# USB.net
KiCad netlist of a schematic drawn in Altium Designer
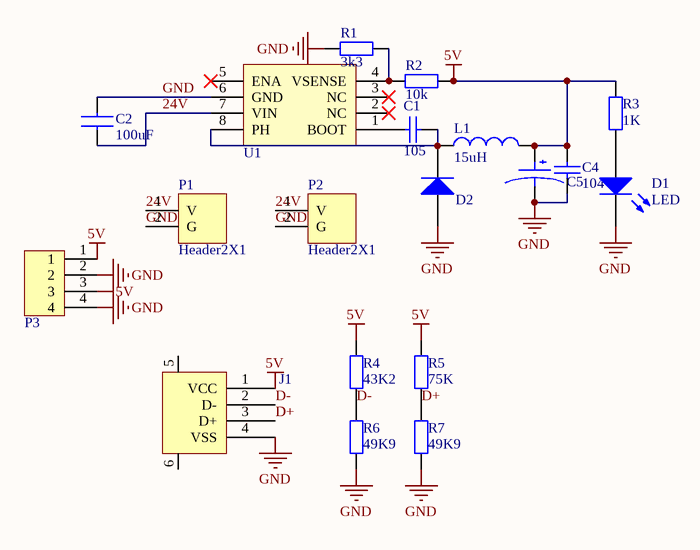
[diagram p0: USB转接板.SchDoc]

(export (version "E")
  (design (tool "Eeschema 10.0.6"))
  (components
    (comp (ref "C1")
      (value "105")
      (footprint "0603C")
      (description "0603/0805")
      (libsource (lib "SHAWN") (part "C_106"))
    )
    (comp (ref "C2") (value "100uF") (footprint "1201C") (libsource (lib "SHAWN") (part "CAP100uF")))
    (comp (ref "C4")
      (value "104")
      (footprint "0603C")
      (description "0603/0805")
      (libsource (lib "SHAWN") (part "C_104"))
    )
    (comp (ref "C5")
      (value "CAP_钽220")
      (footprint "cap_钽E封装")
      (description "CAP")
      (libsource (lib "SHAWN") (part "CAP_钽220"))
    )
    (comp (ref "D1") (value "LED") (footprint "LED_0603") (libsource (lib "SHAWN") (part "LED")))
    (comp (ref "D2")
      (value "Diode_SS34")
      (footprint "Diode_SS34")
      (description "肖特基二极管")
      (libsource (lib "SHAWN") (part "Diode_SS34"))
    )
    (comp (ref "J1")
      (value "USB_seat")
      (footprint "USB_SEAT")
      (description "母座")
      (libsource (lib "SHAWN") (part "USB_seat"))
    )
    (comp (ref "L1")
      (value "15uH")
      (footprint "Inductor7.2X7.2")
      (description "屏蔽电感")
      (libsource (lib "SHAWN") (part "Inductor"))
    )
    (comp (ref "P1")
      (value "Header2X1")
      (footprint "Header_PWR_seat")
      (description "power")
      (libsource (lib "SHAWN") (part "Header2X1"))
    )
    (comp (ref "P2")
      (value "Header2X1")
      (footprint "Header_PWR_seat")
      (description "power")
      (libsource (lib "SHAWN") (part "Header2X1"))
    )
    (comp (ref "P3") (value "Header4") (footprint "Header4_white") (libsource (lib "SHAWN") (part "Header4")))
    (comp (ref "R1")
      (value "3k3")
      (footprint "0603R")
      (description "0603/0805")
      (libsource (lib "") (part "R_1"))
    )
    (comp (ref "R2")
      (value "10k")
      (footprint "0603R")
      (description "0603/0805")
      (libsource (lib "") (part "R_1"))
    )
    (comp (ref "R3")
      (value "1K")
      (footprint "0603R")
      (description "0603/0805")
      (libsource (lib "SHAWN") (part "R"))
    )
    (comp (ref "R4")
      (value "43K2")
      (footprint "0603R")
      (description "0603/0805")
      (libsource (lib "SHAWN") (part "R"))
    )
    (comp (ref "R5")
      (value "75K")
      (footprint "0603R")
      (description "0603/0805")
      (libsource (lib "SHAWN") (part "R"))
    )
    (comp (ref "R6")
      (value "49K9")
      (footprint "0603R")
      (description "0603/0805")
      (libsource (lib "SHAWN") (part "R"))
    )
    (comp (ref "R7")
      (value "49K9")
      (footprint "0603R")
      (description "0603/0805")
      (libsource (lib "SHAWN") (part "R"))
    )
    (comp (ref "U1")
      (value "TPS5430/5450")
      (footprint "TPS5430")
      (description "降压")
      (libsource (lib "SHAWN") (part "TPS5430/5450"))
    )
  )
  (nets
    (net (code "1") (name "/24V") (class "Default")
      (node (ref "C2") (pin "1") (pinfunction "1_1") (pintype "passive"))
      (node (ref "P1") (pin "1") (pinfunction "V_1") (pintype "passive"))
      (node (ref "P2") (pin "1") (pinfunction "V_1") (pintype "passive"))
      (node (ref "U1") (pin "7") (pinfunction "VIN_7") (pintype "passive"))
    )
    (net (code "2") (name "/D+") (class "Default")
      (node (ref "J1") (pin "3") (pinfunction "D+_3") (pintype "passive"))
      (node (ref "R5") (pin "1") (pinfunction "1_1") (pintype "passive"))
      (node (ref "R7") (pin "2") (pinfunction "2_2") (pintype "passive"))
    )
    (net (code "3") (name "/D-") (class "Default")
      (node (ref "J1") (pin "2") (pinfunction "D-_2") (pintype "passive"))
      (node (ref "R4") (pin "1") (pinfunction "1_1") (pintype "passive"))
      (node (ref "R6") (pin "2") (pinfunction "2_2") (pintype "passive"))
    )
    (net (code "4") (name "5V") (class "Default")
      (node (ref "C4") (pin "2") (pinfunction "2_2") (pintype "passive"))
      (node (ref "C5") (pin "2") (pinfunction "2_2") (pintype "passive"))
      (node (ref "J1") (pin "1") (pinfunction "VCC_1") (pintype "passive"))
      (node (ref "L1") (pin "2") (pinfunction "2_2") (pintype "passive"))
      (node (ref "P3") (pin "1") (pinfunction "1_1") (pintype "passive"))
      (node (ref "P3") (pin "3") (pinfunction "3_3") (pintype "passive"))
      (node (ref "R2") (pin "1") (pinfunction "1_1") (pintype "passive"))
      (node (ref "R3") (pin "2") (pinfunction "2_2") (pintype "passive"))
      (node (ref "R4") (pin "2") (pinfunction "2_2") (pintype "passive"))
      (node (ref "R5") (pin "2") (pinfunction "2_2") (pintype "passive"))
    )
    (net (code "5") (name "GND") (class "Default")
      (node (ref "C2") (pin "2") (pinfunction "2_2") (pintype "passive"))
      (node (ref "C4") (pin "1") (pinfunction "1_1") (pintype "passive"))
      (node (ref "C5") (pin "1") (pinfunction "1_1") (pintype "passive"))
      (node (ref "D1") (pin "2") (pinfunction "K_2") (pintype "passive"))
      (node (ref "D2") (pin "1") (pinfunction "A_1") (pintype "passive"))
      (node (ref "J1") (pin "4") (pinfunction "VSS_4") (pintype "passive"))
      (node (ref "P1") (pin "2") (pinfunction "G_2") (pintype "passive"))
      (node (ref "P2") (pin "2") (pinfunction "G_2") (pintype "passive"))
      (node (ref "P3") (pin "2") (pinfunction "2_2") (pintype "passive"))
      (node (ref "P3") (pin "4") (pinfunction "4_4") (pintype "passive"))
      (node (ref "R1") (pin "2") (pinfunction "2_2") (pintype "passive"))
      (node (ref "R6") (pin "1") (pinfunction "1_1") (pintype "passive"))
      (node (ref "R7") (pin "1") (pinfunction "1_1") (pintype "passive"))
      (node (ref "U1") (pin "6") (pinfunction "GND_6") (pintype "passive"))
    )
    (net (code "6") (name "Net-(D1-A)") (class "Default")
      (node (ref "D1") (pin "1") (pinfunction "A_1") (pintype "passive"))
      (node (ref "R3") (pin "1") (pinfunction "1_1") (pintype "passive"))
    )
    (net (code "7") (name "Net-(D2-K)") (class "Default")
      (node (ref "C1") (pin "1") (pinfunction "1_1") (pintype "passive"))
      (node (ref "D2") (pin "2") (pinfunction "K_2") (pintype "passive"))
      (node (ref "L1") (pin "1") (pinfunction "1_1") (pintype "passive"))
      (node (ref "U1") (pin "8") (pinfunction "PH_8") (pintype "passive"))
    )
    (net (code "8") (name "Net-(U1-BOOT)") (class "Default")
      (node (ref "C1") (pin "2") (pinfunction "2_2") (pintype "passive"))
      (node (ref "U1") (pin "1") (pinfunction "BOOT_1") (pintype "passive"))
    )
    (net (code "9") (name "Net-(U1-VSENSE)") (class "Default")
      (node (ref "R1") (pin "1") (pinfunction "1_1") (pintype "passive"))
      (node (ref "R2") (pin "2") (pinfunction "2_2") (pintype "passive"))
      (node (ref "U1") (pin "4") (pinfunction "VSENSE_4") (pintype "passive"))
    )
    (net (code "10") (name "unconnected-(J1-Pad5)") (class "Default")
      (node (ref "J1") (pin "5") (pinfunction "5_5") (pintype "passive"))
    )
    (net (code "11") (name "unconnected-(J1-Pad6)") (class "Default")
      (node (ref "J1") (pin "6") (pinfunction "6_6") (pintype "passive"))
    )
    (net (code "12") (name "unconnected-(U1-ENA-Pad5)") (class "Default")
      (node (ref "U1") (pin "5") (pinfunction "ENA_5") (pintype "passive+no_connect"))
    )
    (net (code "13") (name "unconnected-(U1-NC-Pad2)") (class "Default")
      (node (ref "U1") (pin "2") (pinfunction "NC_2") (pintype "passive+no_connect"))
    )
    (net (code "14") (name "unconnected-(U1-NC-Pad3)") (class "Default")
      (node (ref "U1") (pin "3") (pinfunction "NC_3") (pintype "passive+no_connect"))
    )
  )
)
